# rel-num-display.net
KiCad netlist of a schematic drawn in EAGLE
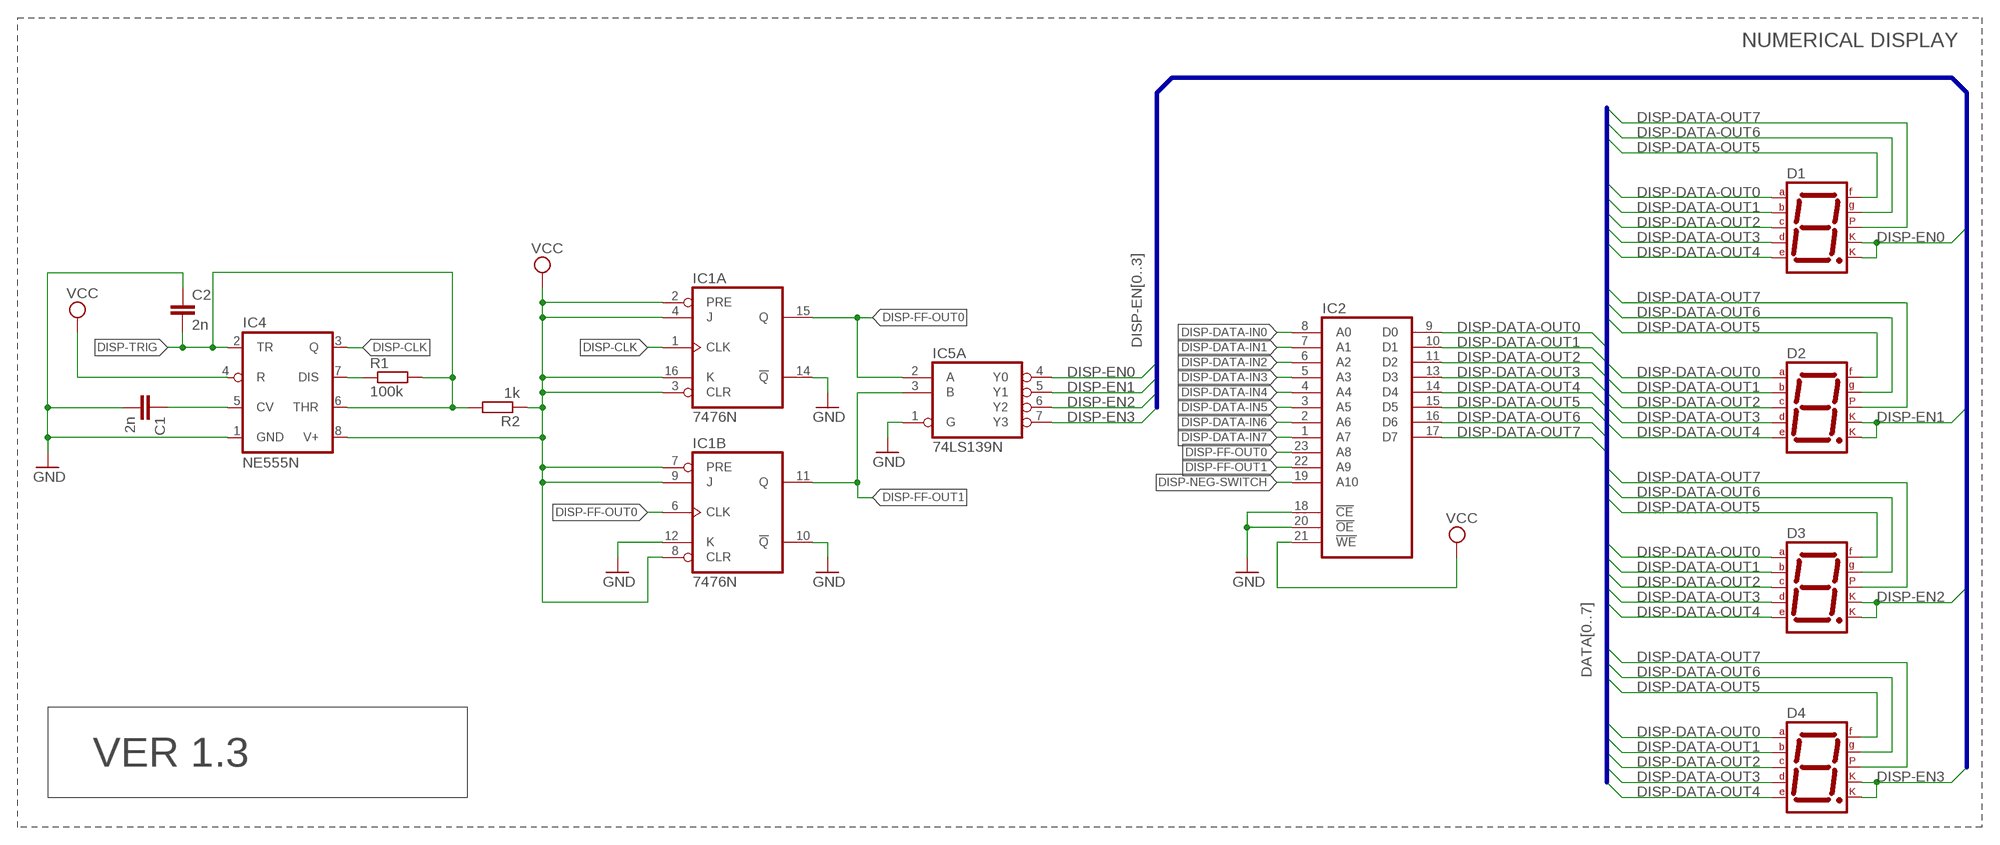
[diagram p0: schematic, sheet 1]

(export (version "E")
  (design (tool "Eeschema 10.0.6"))
  (components
    (comp (ref "C1")
      (value "2n")
      (footprint "eagle-import:C025-025X050")
      (libsource (lib "eagle-import") (part "C-EU025-025X050"))
    )
    (comp (ref "C2")
      (value "2n")
      (footprint "eagle-import:C025-025X050")
      (libsource (lib "eagle-import") (part "C-EU025-025X050"))
    )
    (comp (ref "D1")
      (value "7SEG-CK")
      (footprint "eagle-import:7SEG-13")
      (libsource (lib "eagle-import") (part "7SEG-CK"))
    )
    (comp (ref "D2")
      (value "7SEG-CK")
      (footprint "eagle-import:7SEG-13")
      (libsource (lib "eagle-import") (part "7SEG-CK"))
    )
    (comp (ref "D3")
      (value "7SEG-CK")
      (footprint "eagle-import:7SEG-13")
      (libsource (lib "eagle-import") (part "7SEG-CK"))
    )
    (comp (ref "D4")
      (value "7SEG-CK")
      (footprint "eagle-import:7SEG-13")
      (libsource (lib "eagle-import") (part "7SEG-CK"))
    )
    (comp (ref "IC1")
      (value "7476N")
      (footprint "eagle-import:DIL16")
      (libsource (lib "eagle-import") (part "7476N"))
    )
    (comp (ref "IC2")
      (value "2816")
      (footprint "eagle-import:DIL24")
      (libsource (lib "eagle-import") (part "2816"))
    )
    (comp (ref "IC4")
      (value "NE555N")
      (footprint "eagle-import:DIL08")
      (libsource (lib "eagle-import") (part "555NNE"))
    )
    (comp (ref "IC5")
      (value "74LS139N")
      (footprint "eagle-import:DIL16")
      (libsource (lib "eagle-import") (part "74139NLS"))
    )
    (comp (ref "R1")
      (value "100k")
      (footprint "eagle-import:0204_5")
      (libsource (lib "eagle-import") (part "R-EU_0204/5"))
    )
    (comp (ref "R2")
      (value "1k")
      (footprint "eagle-import:0204_5")
      (libsource (lib "eagle-import") (part "R-EU_0204/5"))
    )
  )
  (nets
    (net (code "10") (name "/DISP-DATA-OUT0") (class "Default")
      (node (ref "D1") (pin "7") (pinfunction "A_7") (pintype "passive"))
      (node (ref "D2") (pin "7") (pinfunction "A_7") (pintype "passive"))
      (node (ref "D3") (pin "7") (pinfunction "A_7") (pintype "passive"))
      (node (ref "D4") (pin "7") (pinfunction "A_7") (pintype "passive"))
      (node (ref "IC2") (pin "9") (pinfunction "D0_9") (pintype "bidirectional"))
    )
    (net (code "11") (name "/DISP-DATA-OUT1") (class "Default")
      (node (ref "D1") (pin "6") (pinfunction "B_6") (pintype "passive"))
      (node (ref "D2") (pin "6") (pinfunction "B_6") (pintype "passive"))
      (node (ref "D3") (pin "6") (pinfunction "B_6") (pintype "passive"))
      (node (ref "D4") (pin "6") (pinfunction "B_6") (pintype "passive"))
      (node (ref "IC2") (pin "10") (pinfunction "D1_10") (pintype "bidirectional"))
    )
    (net (code "12") (name "/DISP-DATA-OUT2") (class "Default")
      (node (ref "D1") (pin "4") (pinfunction "C_4") (pintype "passive"))
      (node (ref "D2") (pin "4") (pinfunction "C_4") (pintype "passive"))
      (node (ref "D3") (pin "4") (pinfunction "C_4") (pintype "passive"))
      (node (ref "D4") (pin "4") (pinfunction "C_4") (pintype "passive"))
      (node (ref "IC2") (pin "11") (pinfunction "D2_11") (pintype "bidirectional"))
    )
    (net (code "13") (name "/DISP-DATA-OUT3") (class "Default")
      (node (ref "D1") (pin "2") (pinfunction "D_2") (pintype "passive"))
      (node (ref "D2") (pin "2") (pinfunction "D_2") (pintype "passive"))
      (node (ref "D3") (pin "2") (pinfunction "D_2") (pintype "passive"))
      (node (ref "D4") (pin "2") (pinfunction "D_2") (pintype "passive"))
      (node (ref "IC2") (pin "13") (pinfunction "D3_13") (pintype "bidirectional"))
    )
    (net (code "14") (name "/DISP-DATA-OUT4") (class "Default")
      (node (ref "D1") (pin "1") (pinfunction "E_1") (pintype "passive"))
      (node (ref "D2") (pin "1") (pinfunction "E_1") (pintype "passive"))
      (node (ref "D3") (pin "1") (pinfunction "E_1") (pintype "passive"))
      (node (ref "D4") (pin "1") (pinfunction "E_1") (pintype "passive"))
      (node (ref "IC2") (pin "14") (pinfunction "D4_14") (pintype "bidirectional"))
    )
    (net (code "15") (name "/DISP-DATA-OUT5") (class "Default")
      (node (ref "D1") (pin "9") (pinfunction "F_9") (pintype "passive"))
      (node (ref "D2") (pin "9") (pinfunction "F_9") (pintype "passive"))
      (node (ref "D3") (pin "9") (pinfunction "F_9") (pintype "passive"))
      (node (ref "D4") (pin "9") (pinfunction "F_9") (pintype "passive"))
      (node (ref "IC2") (pin "15") (pinfunction "D5_15") (pintype "bidirectional"))
    )
    (net (code "16") (name "/DISP-DATA-OUT6") (class "Default")
      (node (ref "D1") (pin "10") (pinfunction "G_10") (pintype "passive"))
      (node (ref "D2") (pin "10") (pinfunction "G_10") (pintype "passive"))
      (node (ref "D3") (pin "10") (pinfunction "G_10") (pintype "passive"))
      (node (ref "D4") (pin "10") (pinfunction "G_10") (pintype "passive"))
      (node (ref "IC2") (pin "16") (pinfunction "D6_16") (pintype "bidirectional"))
    )
    (net (code "17") (name "/DISP-DATA-OUT7") (class "Default")
      (node (ref "D1") (pin "5") (pinfunction "DP_5") (pintype "passive"))
      (node (ref "D2") (pin "5") (pinfunction "DP_5") (pintype "passive"))
      (node (ref "D3") (pin "5") (pinfunction "DP_5") (pintype "passive"))
      (node (ref "D4") (pin "5") (pinfunction "DP_5") (pintype "passive"))
      (node (ref "IC2") (pin "17") (pinfunction "D7_17") (pintype "bidirectional"))
    )
    (net (code "18") (name "/DISP-EN0") (class "Default")
      (node (ref "D1") (pin "3") (pinfunction "CK1_3") (pintype "passive"))
      (node (ref "D1") (pin "8") (pinfunction "CK2_8") (pintype "passive"))
      (node (ref "IC5") (pin "4") (pinfunction "Y0_4") (pintype "output"))
    )
    (net (code "19") (name "/DISP-EN1") (class "Default")
      (node (ref "D2") (pin "3") (pinfunction "CK1_3") (pintype "passive"))
      (node (ref "D2") (pin "8") (pinfunction "CK2_8") (pintype "passive"))
      (node (ref "IC5") (pin "5") (pinfunction "Y1_5") (pintype "output"))
    )
    (net (code "20") (name "/DISP-EN2") (class "Default")
      (node (ref "D3") (pin "3") (pinfunction "CK1_3") (pintype "passive"))
      (node (ref "D3") (pin "8") (pinfunction "CK2_8") (pintype "passive"))
      (node (ref "IC5") (pin "6") (pinfunction "Y2_6") (pintype "output"))
    )
    (net (code "21") (name "/DISP-EN3") (class "Default")
      (node (ref "D4") (pin "3") (pinfunction "CK1_3") (pintype "passive"))
      (node (ref "D4") (pin "8") (pinfunction "CK2_8") (pintype "passive"))
      (node (ref "IC5") (pin "7") (pinfunction "Y3_7") (pintype "output"))
    )
    (net (code "23") (name "DISP-CLK") (class "Default")
      (node (ref "IC1") (pin "1") (pinfunction "CLK_1") (pintype "input"))
      (node (ref "IC4") (pin "3") (pinfunction "Q_3") (pintype "output"))
    )
    (net (code "24") (name "DISP-DATA-IN0") (class "Default")
      (node (ref "IC2") (pin "8") (pinfunction "A0_8") (pintype "input"))
    )
    (net (code "25") (name "DISP-DATA-IN1") (class "Default")
      (node (ref "IC2") (pin "7") (pinfunction "A1_7") (pintype "input"))
    )
    (net (code "26") (name "DISP-DATA-IN2") (class "Default")
      (node (ref "IC2") (pin "6") (pinfunction "A2_6") (pintype "input"))
    )
    (net (code "27") (name "DISP-DATA-IN3") (class "Default")
      (node (ref "IC2") (pin "5") (pinfunction "A3_5") (pintype "input"))
    )
    (net (code "28") (name "DISP-DATA-IN4") (class "Default")
      (node (ref "IC2") (pin "4") (pinfunction "A4_4") (pintype "input"))
    )
    (net (code "29") (name "DISP-DATA-IN5") (class "Default")
      (node (ref "IC2") (pin "3") (pinfunction "A5_3") (pintype "input"))
    )
    (net (code "30") (name "DISP-DATA-IN6") (class "Default")
      (node (ref "IC2") (pin "2") (pinfunction "A6_2") (pintype "input"))
    )
    (net (code "31") (name "DISP-DATA-IN7") (class "Default")
      (node (ref "IC2") (pin "1") (pinfunction "A7_1") (pintype "input"))
    )
    (net (code "32") (name "DISP-FF-OUT0") (class "Default")
      (node (ref "IC1") (pin "15") (pinfunction "Q_15") (pintype "output"))
      (node (ref "IC1") (pin "6") (pinfunction "CLK_6") (pintype "input"))
      (node (ref "IC2") (pin "23") (pinfunction "A8_23") (pintype "input"))
      (node (ref "IC5") (pin "2") (pinfunction "A_2") (pintype "input"))
    )
    (net (code "33") (name "DISP-FF-OUT1") (class "Default")
      (node (ref "IC1") (pin "11") (pinfunction "Q_11") (pintype "output"))
      (node (ref "IC2") (pin "22") (pinfunction "A9_22") (pintype "input"))
      (node (ref "IC5") (pin "3") (pinfunction "B_3") (pintype "input"))
    )
    (net (code "34") (name "DISP-NEG-SWITCH") (class "Default")
      (node (ref "IC2") (pin "19") (pinfunction "A10_19") (pintype "input"))
    )
    (net (code "35") (name "DISP-TRIG") (class "Default")
      (node (ref "C2") (pin "2") (pinfunction "2_2") (pintype "passive"))
      (node (ref "IC4") (pin "2") (pinfunction "TR_2") (pintype "input"))
      (node (ref "IC4") (pin "6") (pinfunction "THR_6") (pintype "input"))
      (node (ref "R1") (pin "2") (pinfunction "2_2") (pintype "passive"))
      (node (ref "R2") (pin "2") (pinfunction "2_2") (pintype "passive"))
    )
    (net (code "36") (name "GND") (class "Default")
      (node (ref "C1") (pin "2") (pinfunction "2_2") (pintype "passive"))
      (node (ref "C2") (pin "1") (pinfunction "1_1") (pintype "passive"))
      (node (ref "IC1") (pin "10") (pinfunction "~{Q}_10") (pintype "output"))
      (node (ref "IC1") (pin "12") (pinfunction "K_12") (pintype "input"))
      (node (ref "IC1") (pin "14") (pinfunction "~{Q}_14") (pintype "output"))
      (node (ref "IC2") (pin "18") (pinfunction "~{CE}_18") (pintype "input"))
      (node (ref "IC2") (pin "20") (pinfunction "~{OE}_20") (pintype "input"))
      (node (ref "IC4") (pin "1") (pinfunction "GND_1") (pintype "power_in"))
      (node (ref "IC5") (pin "1") (pinfunction "G_1") (pintype "input"))
    )
    (net (code "37") (name "Net-(IC4-CV)") (class "Default")
      (node (ref "C1") (pin "1") (pinfunction "1_1") (pintype "passive"))
      (node (ref "IC4") (pin "5") (pinfunction "CV_5") (pintype "input"))
    )
    (net (code "38") (name "Net-(IC4-DIS)") (class "Default")
      (node (ref "IC4") (pin "7") (pinfunction "DIS_7") (pintype "input"))
      (node (ref "R1") (pin "1") (pinfunction "1_1") (pintype "passive"))
    )
    (net (code "39") (name "VCC") (class "Default")
      (node (ref "IC1") (pin "16") (pinfunction "K_16") (pintype "input"))
      (node (ref "IC1") (pin "2") (pinfunction "PRE_2") (pintype "input"))
      (node (ref "IC1") (pin "3") (pinfunction "CLR_3") (pintype "input"))
      (node (ref "IC1") (pin "4") (pinfunction "J_4") (pintype "input"))
      (node (ref "IC1") (pin "7") (pinfunction "PRE_7") (pintype "input"))
      (node (ref "IC1") (pin "8") (pinfunction "CLR_8") (pintype "input"))
      (node (ref "IC1") (pin "9") (pinfunction "J_9") (pintype "input"))
      (node (ref "IC2") (pin "21") (pinfunction "~{WE}_21") (pintype "input"))
      (node (ref "IC4") (pin "4") (pinfunction "R_4") (pintype "input"))
      (node (ref "IC4") (pin "8") (pinfunction "V+_8") (pintype "power_in"))
      (node (ref "R2") (pin "1") (pinfunction "1_1") (pintype "passive"))
    )
  )
)
